# MINI_SAM_D21_r001_b001.net
KiCad netlist of a schematic drawn in EAGLE
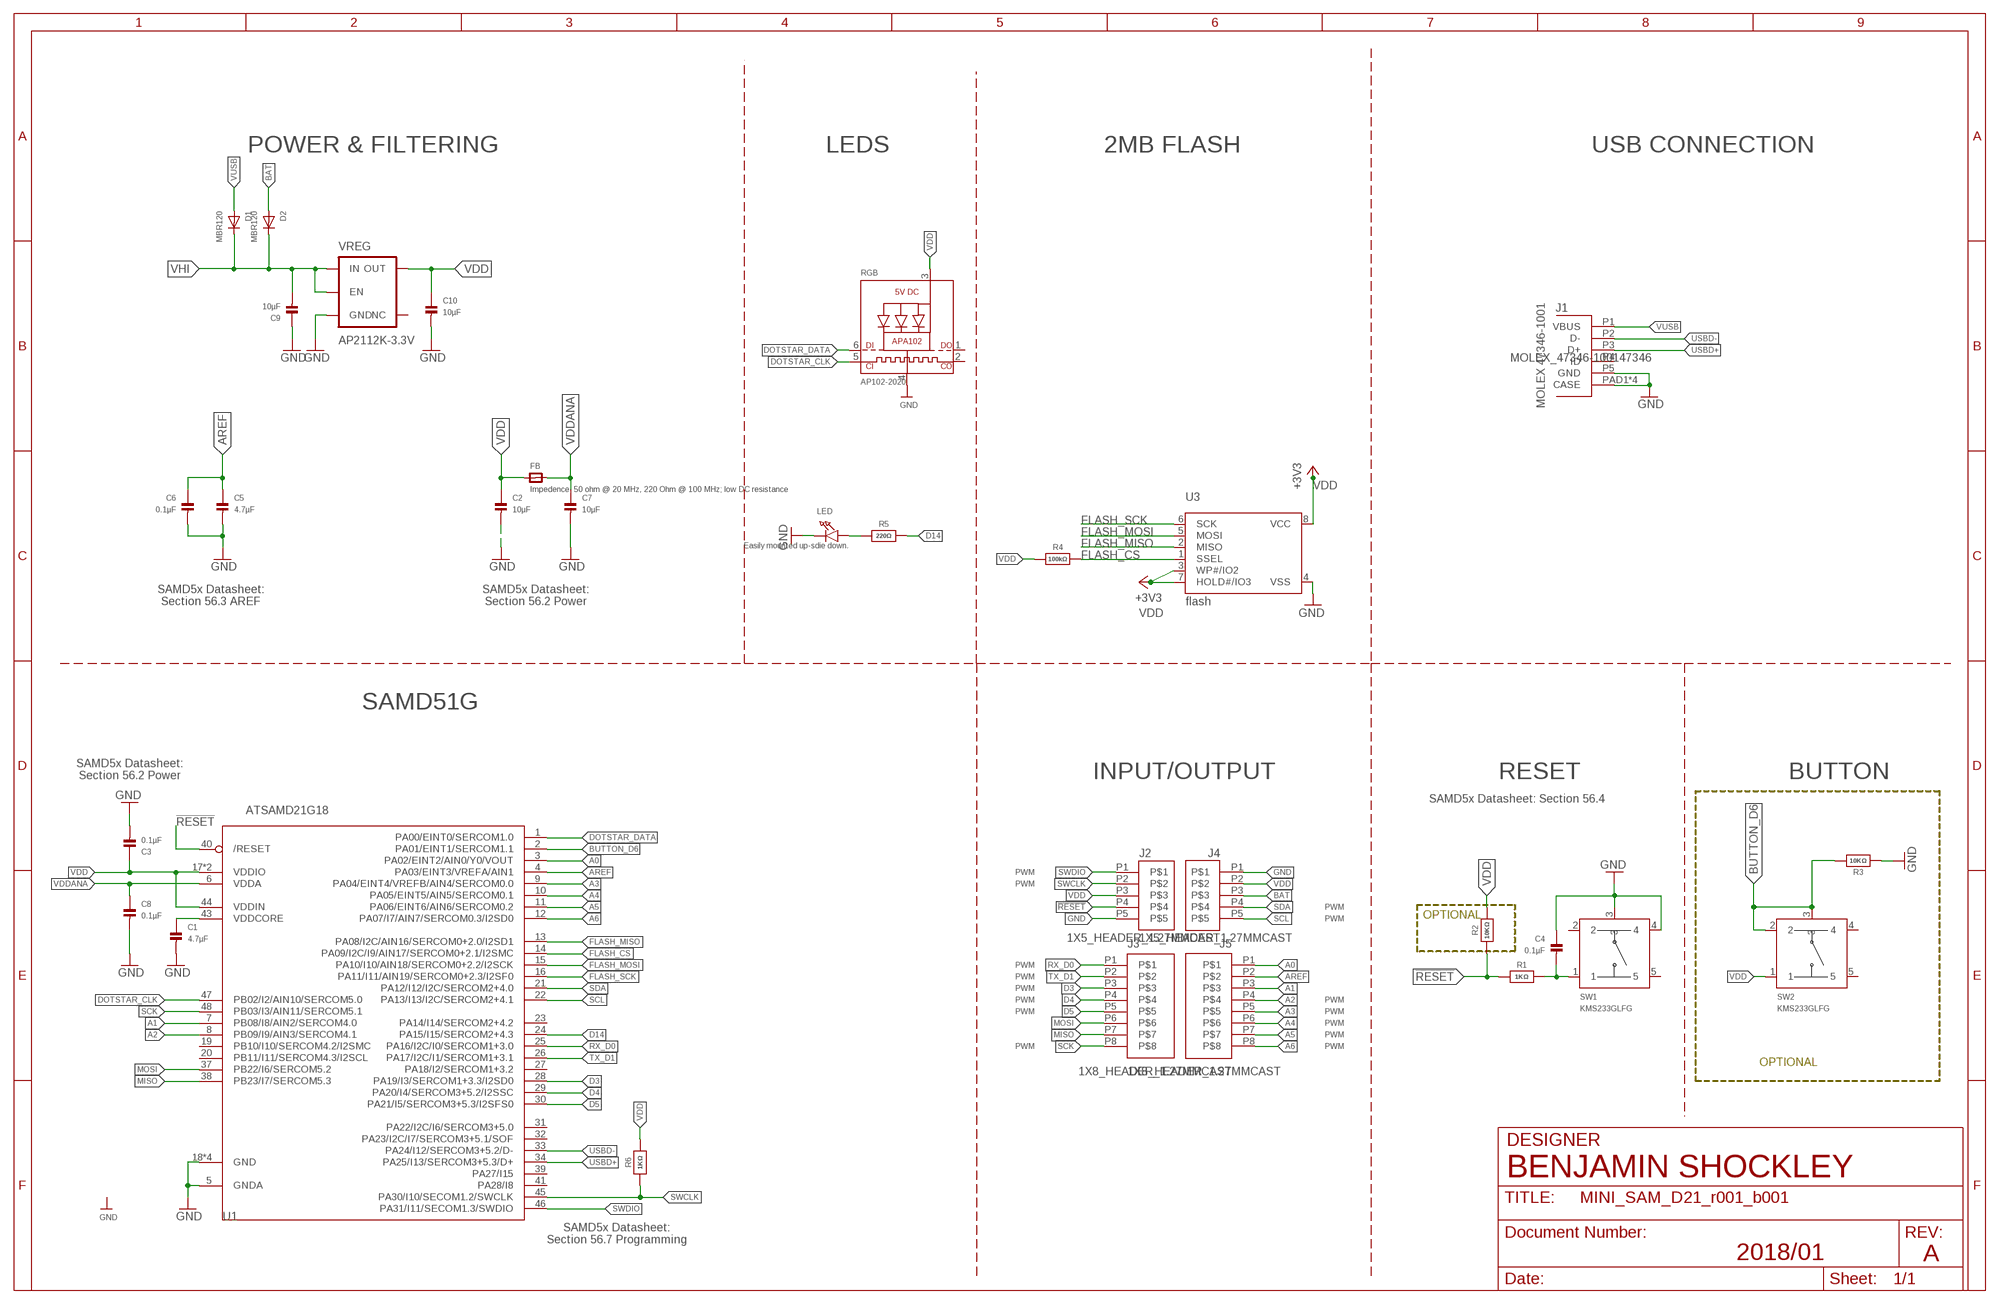
[diagram p0: schematic, sheet 1]

(export (version "E")
  (design (tool "Eeschema 10.0.6"))
  (components
    (comp (ref "C1")
      (value "4.7µF")
      (footprint "eagle-import:_0603MP")
      (libsource (lib "eagle-import") (part "CAP_CERAMIC_0603MP"))
    )
    (comp (ref "C2")
      (value "10µF")
      (footprint "eagle-import:_0603MP")
      (libsource (lib "eagle-import") (part "CAP_CERAMIC_0603MP"))
    )
    (comp (ref "C3")
      (value "0.1µF")
      (footprint "eagle-import:_0603MP")
      (libsource (lib "eagle-import") (part "CAP_CERAMIC_0603MP"))
    )
    (comp (ref "C4")
      (value "0.1µF")
      (footprint "eagle-import:_0603MP")
      (libsource (lib "eagle-import") (part "CAP_CERAMIC_0603MP"))
    )
    (comp (ref "C5")
      (value "4.7µF")
      (footprint "eagle-import:_0603MP")
      (libsource (lib "eagle-import") (part "CAP_CERAMIC_0603MP"))
    )
    (comp (ref "C6")
      (value "0.1µF")
      (footprint "eagle-import:_0603MP")
      (libsource (lib "eagle-import") (part "CAP_CERAMIC_0603MP"))
    )
    (comp (ref "C7")
      (value "10µF")
      (footprint "eagle-import:_0603MP")
      (libsource (lib "eagle-import") (part "CAP_CERAMIC_0603MP"))
    )
    (comp (ref "C8")
      (value "0.1µF")
      (footprint "eagle-import:_0603MP")
      (libsource (lib "eagle-import") (part "CAP_CERAMIC_0603MP"))
    )
    (comp (ref "C9")
      (value "10µF")
      (footprint "eagle-import:_0603MP")
      (libsource (lib "eagle-import") (part "CAP_CERAMIC_0603MP"))
    )
    (comp (ref "C10")
      (value "10µF")
      (footprint "eagle-import:_0603MP")
      (libsource (lib "eagle-import") (part "CAP_CERAMIC_0603MP"))
    )
    (comp (ref "D1")
      (value "MBR120")
      (footprint "eagle-import:SOD-123FL")
      (libsource (lib "eagle-import") (part "DIODE_SOD-123FL"))
    )
    (comp (ref "D2")
      (value "MBR120")
      (footprint "eagle-import:SOD-123FL")
      (libsource (lib "eagle-import") (part "DIODE_SOD-123FL"))
    )
    (comp (ref "FB")
      (value "Impedence: 50 ohm @ 20 MHz, 220 Ohm @ 100 MHz; low DC resistance")
      (footprint "eagle-import:_0603MP")
      (libsource (lib "eagle-import") (part "FERRITE_0603MP"))
    )
    (comp (ref "J1")
      (value "MOLEX_47346-100147346")
      (footprint "eagle-import:MOLEX_47346-1001")
      (libsource (lib "eagle-import") (part "MOLEX_47346-100147346"))
    )
    (comp (ref "J2")
      (value "1X5_HEADER_1.27MMCAST")
      (footprint "eagle-import:1X5_HEADER_1.27MM_CASTELLATED")
      (libsource (lib "eagle-import") (part "1X5_HEADER_1.27MMCAST"))
    )
    (comp (ref "J3")
      (value "1X8_HEADER_1.27MMCAST")
      (footprint "eagle-import:1X8_HEADER_1.27MM_CASTELLATED")
      (libsource (lib "eagle-import") (part "1X8_HEADER_1.27MMCAST"))
    )
    (comp (ref "J4")
      (value "1X5_HEADER_1.27MMCAST")
      (footprint "eagle-import:1X5_HEADER_1.27MM_CASTELLATED")
      (libsource (lib "eagle-import") (part "1X5_HEADER_1.27MMCAST"))
    )
    (comp (ref "J5")
      (value "1X8_HEADER_1.27MMCAST")
      (footprint "eagle-import:1X8_HEADER_1.27MM_CASTELLATED")
      (libsource (lib "eagle-import") (part "1X8_HEADER_1.27MMCAST"))
    )
    (comp (ref "LED")
      (value "Easily mounted up-sdie down.")
      (footprint "eagle-import:CHIPLED_0805_NOOUTLINE")
      (libsource (lib "eagle-import") (part "LED0805_NOOUTLINE"))
    )
    (comp (ref "R1")
      (value "1KΩ")
      (footprint "eagle-import:_0603MP")
      (libsource (lib "eagle-import") (part "RESISTOR_0603MP"))
    )
    (comp (ref "R2")
      (value "10KΩ")
      (footprint "eagle-import:_0603MP")
      (libsource (lib "eagle-import") (part "RESISTOR_0603MP"))
    )
    (comp (ref "R3")
      (value "10KΩ")
      (footprint "eagle-import:_0603MP")
      (libsource (lib "eagle-import") (part "RESISTOR_0603MP"))
    )
    (comp (ref "R4")
      (value "100kΩ")
      (footprint "eagle-import:_0603MP")
      (libsource (lib "eagle-import") (part "RESISTOR_0603MP"))
    )
    (comp (ref "R5")
      (value "220Ω")
      (footprint "eagle-import:_0603MP")
      (libsource (lib "eagle-import") (part "RESISTOR_0603MP"))
    )
    (comp (ref "R6")
      (value "1KΩ")
      (footprint "eagle-import:_0603MP")
      (libsource (lib "eagle-import") (part "RESISTOR_0603MP"))
    )
    (comp (ref "RGB")
      (value "AP102-2020")
      (footprint "eagle-import:APA102_2020")
      (libsource (lib "eagle-import") (part "APA1022020"))
    )
    (comp (ref "SW1")
      (value "KMS233GLFG")
      (footprint "eagle-import:KMS_SWITCH")
      (libsource (lib "eagle-import") (part "KMS_SWITCHKMS"))
    )
    (comp (ref "SW2")
      (value "KMS233GLFG")
      (footprint "eagle-import:KMS_SWITCH")
      (libsource (lib "eagle-import") (part "KMS_SWITCHKMS"))
    )
    (comp (ref "U1")
      (value "ATSAMD21G18")
      (footprint "eagle-import:TQFN48_7MM")
      (libsource (lib "eagle-import") (part "ATSAMD21G_QFN"))
    )
    (comp (ref "U3")
      (value "flash")
      (footprint "eagle-import:USON8")
      (libsource (lib "eagle-import") (part "SPIFLASH_8PINUX"))
    )
    (comp (ref "VREG")
      (value "AP2112K-3.3V")
      (footprint "eagle-import:SOT23-5")
      (libsource (lib "eagle-import") (part "V_REG_AP2112K-3.3V"))
    )
  )
  (nets
    (net (code "1") (name "/~{RESET}") (class "Default")
      (node (ref "J2") (pin "P4") (pinfunction "P$4_P4") (pintype "bidirectional"))
      (node (ref "R1") (pin "1") (pinfunction "1_1") (pintype "passive"))
      (node (ref "R2") (pin "1") (pinfunction "1_1") (pintype "passive"))
      (node (ref "U1") (pin "40") (pinfunction "/RESET_40") (pintype "bidirectional"))
    )
    (net (code "2") (name "A0") (class "Default")
      (node (ref "J5") (pin "P1") (pinfunction "P$1_P1") (pintype "bidirectional"))
      (node (ref "U1") (pin "3") (pinfunction "PA02/EINT2/AIN0/Y0/VOUT_3") (pintype "bidirectional"))
    )
    (net (code "3") (name "A1") (class "Default")
      (node (ref "J5") (pin "P3") (pinfunction "P$3_P3") (pintype "bidirectional"))
      (node (ref "U1") (pin "7") (pinfunction "PB08/I8/AIN2/SERCOM4.0_7") (pintype "bidirectional"))
    )
    (net (code "4") (name "A2") (class "Default")
      (node (ref "J5") (pin "P4") (pinfunction "P$4_P4") (pintype "bidirectional"))
      (node (ref "U1") (pin "8") (pinfunction "PB09/I9/AIN3/SERCOM4.1_8") (pintype "bidirectional"))
    )
    (net (code "5") (name "A3") (class "Default")
      (node (ref "J5") (pin "P5") (pinfunction "P$5_P5") (pintype "bidirectional"))
      (node (ref "U1") (pin "9") (pinfunction "PA04/EINT4/VREFB/AIN4/SERCOM0.0_9") (pintype "bidirectional"))
    )
    (net (code "6") (name "A4") (class "Default")
      (node (ref "J5") (pin "P6") (pinfunction "P$6_P6") (pintype "bidirectional"))
      (node (ref "U1") (pin "10") (pinfunction "PA05/EINT5/AIN5/SERCOM0.1_10") (pintype "bidirectional"))
    )
    (net (code "7") (name "A5") (class "Default")
      (node (ref "J5") (pin "P7") (pinfunction "P$7_P7") (pintype "bidirectional"))
      (node (ref "U1") (pin "11") (pinfunction "PA06/EINT6/AIN6/SERCOM0.2_11") (pintype "bidirectional"))
    )
    (net (code "8") (name "A6") (class "Default")
      (node (ref "J5") (pin "P8") (pinfunction "P$8_P8") (pintype "bidirectional"))
      (node (ref "U1") (pin "12") (pinfunction "PA07/I7/AIN7/SERCOM0.3/I2SD0_12") (pintype "bidirectional"))
    )
    (net (code "9") (name "AREF") (class "Default")
      (node (ref "C5") (pin "1") (pinfunction "P$1_1") (pintype "passive"))
      (node (ref "C6") (pin "1") (pinfunction "P$1_1") (pintype "passive"))
      (node (ref "J5") (pin "P2") (pinfunction "P$2_P2") (pintype "bidirectional"))
      (node (ref "U1") (pin "4") (pinfunction "PA03/EINT3/VREFA/AIN1_4") (pintype "bidirectional"))
    )
    (net (code "10") (name "BAT") (class "Default")
      (node (ref "D2") (pin "A") (pinfunction "A_A") (pintype "passive"))
      (node (ref "J4") (pin "P3") (pinfunction "P$3_P3") (pintype "bidirectional"))
    )
    (net (code "11") (name "BUTTON_D6") (class "Default")
      (node (ref "R3") (pin "2") (pinfunction "2_2") (pintype "passive"))
      (node (ref "SW2") (pin "2") (pinfunction "2_2") (pintype "bidirectional"))
      (node (ref "SW2") (pin "3") (pinfunction "3_3") (pintype "bidirectional"))
      (node (ref "U1") (pin "2") (pinfunction "PA01/EINT1/SERCOM1.1_2") (pintype "bidirectional"))
    )
    (net (code "12") (name "D3") (class "Default")
      (node (ref "J3") (pin "P3") (pinfunction "P$3_P3") (pintype "bidirectional"))
      (node (ref "U1") (pin "28") (pinfunction "PA19/I3/SERCOM1+3.3/I2SD0_28") (pintype "bidirectional"))
    )
    (net (code "13") (name "D4") (class "Default")
      (node (ref "J3") (pin "P4") (pinfunction "P$4_P4") (pintype "bidirectional"))
      (node (ref "U1") (pin "29") (pinfunction "PA20/I4/SERCOM3+5.2/I2SSC_29") (pintype "bidirectional"))
    )
    (net (code "14") (name "D5") (class "Default")
      (node (ref "J3") (pin "P5") (pinfunction "P$5_P5") (pintype "bidirectional"))
      (node (ref "U1") (pin "30") (pinfunction "PA21/I5/SERCOM3+5.3/I2SFS0_30") (pintype "bidirectional"))
    )
    (net (code "15") (name "D14") (class "Default")
      (node (ref "R5") (pin "2") (pinfunction "2_2") (pintype "passive"))
      (node (ref "U1") (pin "24") (pinfunction "PA15/I15/SERCOM2+4.3_24") (pintype "bidirectional"))
    )
    (net (code "16") (name "DOTSTAR_CLK") (class "Default")
      (node (ref "RGB") (pin "5") (pinfunction "CKI_5") (pintype "input"))
      (node (ref "U1") (pin "47") (pinfunction "PB02/I2/AIN10/SERCOM5.0_47") (pintype "bidirectional"))
    )
    (net (code "17") (name "DOTSTAR_DATA") (class "Default")
      (node (ref "RGB") (pin "6") (pinfunction "DI_6") (pintype "input"))
      (node (ref "U1") (pin "1") (pinfunction "PA00/EINT0/SERCOM1.0_1") (pintype "bidirectional"))
    )
    (net (code "18") (name "FLASH_CS") (class "Default")
      (node (ref "R4") (pin "2") (pinfunction "2_2") (pintype "passive"))
      (node (ref "U1") (pin "14") (pinfunction "PA09/I2C/I9/AIN17/SERCOM0+2.1/I2SMC_14") (pintype "bidirectional"))
      (node (ref "U3") (pin "1") (pinfunction "SSEL_1") (pintype "bidirectional"))
    )
    (net (code "19") (name "FLASH_MISO") (class "Default")
      (node (ref "U1") (pin "13") (pinfunction "PA08/I2C/AIN16/SERCOM0+2.0/I2SD1_13") (pintype "bidirectional"))
      (node (ref "U3") (pin "2") (pinfunction "MISO_2") (pintype "bidirectional"))
    )
    (net (code "20") (name "FLASH_MOSI") (class "Default")
      (node (ref "U1") (pin "15") (pinfunction "PA10/I10/AIN18/SERCOM0+2.2/I2SCK_15") (pintype "bidirectional"))
      (node (ref "U3") (pin "5") (pinfunction "MOSI_5") (pintype "bidirectional"))
    )
    (net (code "21") (name "FLASH_SCK") (class "Default")
      (node (ref "U1") (pin "16") (pinfunction "PA11/I11/AIN19/SERCOM0+2.3/I2SF0_16") (pintype "bidirectional"))
      (node (ref "U3") (pin "6") (pinfunction "SCK_6") (pintype "bidirectional"))
    )
    (net (code "22") (name "GND") (class "Default")
      (node (ref "C1") (pin "2") (pinfunction "P$2_2") (pintype "passive"))
      (node (ref "C10") (pin "2") (pinfunction "P$2_2") (pintype "passive"))
      (node (ref "C2") (pin "2") (pinfunction "P$2_2") (pintype "passive"))
      (node (ref "C3") (pin "2") (pinfunction "P$2_2") (pintype "passive"))
      (node (ref "C4") (pin "1") (pinfunction "P$1_1") (pintype "passive"))
      (node (ref "C5") (pin "2") (pinfunction "P$2_2") (pintype "passive"))
      (node (ref "C6") (pin "2") (pinfunction "P$2_2") (pintype "passive"))
      (node (ref "C7") (pin "2") (pinfunction "P$2_2") (pintype "passive"))
      (node (ref "C8") (pin "2") (pinfunction "P$2_2") (pintype "passive"))
      (node (ref "C9") (pin "1") (pinfunction "P$1_1") (pintype "passive"))
      (node (ref "J1") (pin "P5") (pinfunction "GND_P5") (pintype "power_in"))
      (node (ref "J1") (pin "PAD1") (pinfunction "CASE_PAD1") (pintype "bidirectional"))
      (node (ref "J1") (pin "PAD2") (pinfunction "CASE_PAD2") (pintype "bidirectional"))
      (node (ref "J1") (pin "PAD3") (pinfunction "CASE_PAD3") (pintype "bidirectional"))
      (node (ref "J1") (pin "PAD4") (pinfunction "CASE_PAD4") (pintype "bidirectional"))
      (node (ref "J2") (pin "P5") (pinfunction "P$5_P5") (pintype "bidirectional"))
      (node (ref "J4") (pin "P1") (pinfunction "P$1_P1") (pintype "bidirectional"))
      (node (ref "LED") (pin "C") (pinfunction "C_C") (pintype "passive"))
      (node (ref "R3") (pin "1") (pinfunction "1_1") (pintype "passive"))
      (node (ref "RGB") (pin "4") (pinfunction "GND_4") (pintype "power_in"))
      (node (ref "SW1") (pin "3") (pinfunction "3_3") (pintype "bidirectional"))
      (node (ref "SW1") (pin "4") (pinfunction "4_4") (pintype "bidirectional"))
      (node (ref "U1") (pin "18") (pinfunction "GND_18") (pintype "power_in"))
      (node (ref "U1") (pin "35") (pinfunction "GND_35") (pintype "power_in"))
      (node (ref "U1") (pin "42") (pinfunction "GND_42") (pintype "power_in"))
      (node (ref "U1") (pin "5") (pinfunction "GNDA_5") (pintype "power_in"))
      (node (ref "U1") (pin "THERMAL") (pinfunction "GND_THERMAL") (pintype "power_in"))
      (node (ref "U3") (pin "4") (pinfunction "VSS_4") (pintype "bidirectional"))
      (node (ref "VREG") (pin "2") (pinfunction "GND_2") (pintype "input"))
    )
    (net (code "23") (name "MISO") (class "Default")
      (node (ref "J3") (pin "P7") (pinfunction "P$7_P7") (pintype "bidirectional"))
      (node (ref "U1") (pin "38") (pinfunction "PB23/I7/SERCOM5.3_38") (pintype "bidirectional"))
    )
    (net (code "24") (name "MOSI") (class "Default")
      (node (ref "J3") (pin "P6") (pinfunction "P$6_P6") (pintype "bidirectional"))
      (node (ref "U1") (pin "37") (pinfunction "PB22/I6/SERCOM5.2_37") (pintype "bidirectional"))
    )
    (net (code "25") (name "Net-(C1-P$1)") (class "Default")
      (node (ref "C1") (pin "1") (pinfunction "P$1_1") (pintype "passive"))
      (node (ref "U1") (pin "43") (pinfunction "VDDCORE_43") (pintype "power_in"))
    )
    (net (code "26") (name "Net-(C4-P$2)") (class "Default")
      (node (ref "C4") (pin "2") (pinfunction "P$2_2") (pintype "passive"))
      (node (ref "R1") (pin "2") (pinfunction "2_2") (pintype "passive"))
      (node (ref "SW1") (pin "1") (pinfunction "1_1") (pintype "bidirectional"))
    )
    (net (code "27") (name "Net-(LED-PadA)") (class "Default")
      (node (ref "LED") (pin "A") (pinfunction "A_A") (pintype "passive"))
      (node (ref "R5") (pin "1") (pinfunction "1_1") (pintype "passive"))
    )
    (net (code "28") (name "RX_D0") (class "Default")
      (node (ref "J3") (pin "P1") (pinfunction "P$1_P1") (pintype "bidirectional"))
      (node (ref "U1") (pin "25") (pinfunction "PA16/I2C/I0/SERCOM1+3.0_25") (pintype "bidirectional"))
    )
    (net (code "29") (name "SCK") (class "Default")
      (node (ref "J3") (pin "P8") (pinfunction "P$8_P8") (pintype "bidirectional"))
      (node (ref "U1") (pin "48") (pinfunction "PB03/I3/AIN11/SERCOM5.1_48") (pintype "bidirectional"))
    )
    (net (code "30") (name "SCL") (class "Default")
      (node (ref "J4") (pin "P5") (pinfunction "P$5_P5") (pintype "bidirectional"))
      (node (ref "U1") (pin "22") (pinfunction "PA13/I13/I2C/SERCOM2+4.1_22") (pintype "bidirectional"))
    )
    (net (code "31") (name "SDA") (class "Default")
      (node (ref "J4") (pin "P4") (pinfunction "P$4_P4") (pintype "bidirectional"))
      (node (ref "U1") (pin "21") (pinfunction "PA12/I12/I2C/SERCOM2+4.0_21") (pintype "bidirectional"))
    )
    (net (code "32") (name "SWCLK") (class "Default")
      (node (ref "J2") (pin "P2") (pinfunction "P$2_P2") (pintype "bidirectional"))
      (node (ref "R6") (pin "1") (pinfunction "1_1") (pintype "passive"))
      (node (ref "U1") (pin "45") (pinfunction "PA30/I10/SECOM1.2/SWCLK_45") (pintype "bidirectional"))
    )
    (net (code "33") (name "SWDIO") (class "Default")
      (node (ref "J2") (pin "P1") (pinfunction "P$1_P1") (pintype "bidirectional"))
      (node (ref "U1") (pin "46") (pinfunction "PA31/I11/SECOM1.3/SWDIO_46") (pintype "bidirectional"))
    )
    (net (code "34") (name "TX_D1") (class "Default")
      (node (ref "J3") (pin "P2") (pinfunction "P$2_P2") (pintype "bidirectional"))
      (node (ref "U1") (pin "26") (pinfunction "PA17/I2C/I1/SERCOM1+3.1_26") (pintype "bidirectional"))
    )
    (net (code "35") (name "USBD+") (class "Default")
      (node (ref "J1") (pin "P3") (pinfunction "D+_P3") (pintype "bidirectional"))
      (node (ref "U1") (pin "34") (pinfunction "PA25/I13/SERCOM3+5.3/D+_34") (pintype "bidirectional"))
    )
    (net (code "36") (name "USBD-") (class "Default")
      (node (ref "J1") (pin "P2") (pinfunction "D-_P2") (pintype "bidirectional"))
      (node (ref "U1") (pin "33") (pinfunction "PA24/I12/SERCOM3+5.2/D-_33") (pintype "bidirectional"))
    )
    (net (code "37") (name "VDD") (class "Default")
      (node (ref "C10") (pin "1") (pinfunction "P$1_1") (pintype "passive"))
      (node (ref "C2") (pin "1") (pinfunction "P$1_1") (pintype "passive"))
      (node (ref "C3") (pin "1") (pinfunction "P$1_1") (pintype "passive"))
      (node (ref "FB") (pin "1") (pinfunction "P$1_1") (pintype "passive"))
      (node (ref "J2") (pin "P3") (pinfunction "P$3_P3") (pintype "bidirectional"))
      (node (ref "J4") (pin "P2") (pinfunction "P$2_P2") (pintype "bidirectional"))
      (node (ref "R2") (pin "2") (pinfunction "2_2") (pintype "passive"))
      (node (ref "R4") (pin "1") (pinfunction "1_1") (pintype "passive"))
      (node (ref "R6") (pin "2") (pinfunction "2_2") (pintype "passive"))
      (node (ref "RGB") (pin "3") (pinfunction "VDD_3") (pintype "power_in"))
      (node (ref "SW2") (pin "1") (pinfunction "1_1") (pintype "bidirectional"))
      (node (ref "U1") (pin "17") (pinfunction "VDDIO_17") (pintype "power_in"))
      (node (ref "U1") (pin "36") (pinfunction "VDDIO_36") (pintype "power_in"))
      (node (ref "U1") (pin "44") (pinfunction "VDDIN_44") (pintype "power_in"))
      (node (ref "U3") (pin "3") (pinfunction "WP#/IO2_3") (pintype "bidirectional"))
      (node (ref "U3") (pin "7") (pinfunction "HOLD#/IO3_7") (pintype "bidirectional"))
      (node (ref "U3") (pin "8") (pinfunction "VCC_8") (pintype "bidirectional"))
      (node (ref "VREG") (pin "5") (pinfunction "OUT_5") (pintype "passive"))
    )
    (net (code "38") (name "VDDANA") (class "Default")
      (node (ref "C7") (pin "1") (pinfunction "P$1_1") (pintype "passive"))
      (node (ref "C8") (pin "1") (pinfunction "P$1_1") (pintype "passive"))
      (node (ref "FB") (pin "2") (pinfunction "P$2_2") (pintype "passive"))
      (node (ref "U1") (pin "6") (pinfunction "VDDA_6") (pintype "power_in"))
    )
    (net (code "39") (name "VHI") (class "Default")
      (node (ref "C9") (pin "2") (pinfunction "P$2_2") (pintype "passive"))
      (node (ref "D1") (pin "C") (pinfunction "C_C") (pintype "passive"))
      (node (ref "D2") (pin "C") (pinfunction "C_C") (pintype "passive"))
      (node (ref "VREG") (pin "1") (pinfunction "IN_1") (pintype "input"))
      (node (ref "VREG") (pin "3") (pinfunction "EN_3") (pintype "input"))
    )
    (net (code "40") (name "VUSB") (class "Default")
      (node (ref "D1") (pin "A") (pinfunction "A_A") (pintype "passive"))
      (node (ref "J1") (pin "P1") (pinfunction "VBUS_P1") (pintype "power_in"))
    )
    (net (code "41") (name "unconnected-(J1-ID-PadP4)") (class "Default")
      (node (ref "J1") (pin "P4") (pinfunction "ID_P4") (pintype "bidirectional"))
    )
    (net (code "42") (name "unconnected-(RGB-CKO-Pad2)") (class "Default")
      (node (ref "RGB") (pin "2") (pinfunction "CKO_2") (pintype "output"))
    )
    (net (code "43") (name "unconnected-(RGB-DO-Pad1)") (class "Default")
      (node (ref "RGB") (pin "1") (pinfunction "DO_1") (pintype "output"))
    )
    (net (code "44") (name "unconnected-(SW1-Pad2)") (class "Default")
      (node (ref "SW1") (pin "2") (pinfunction "2_2") (pintype "bidirectional"))
    )
    (net (code "45") (name "unconnected-(SW1-Pad5)") (class "Default")
      (node (ref "SW1") (pin "5") (pinfunction "5_5") (pintype "bidirectional"))
    )
    (net (code "46") (name "unconnected-(SW2-Pad4)") (class "Default")
      (node (ref "SW2") (pin "4") (pinfunction "4_4") (pintype "bidirectional"))
    )
    (net (code "47") (name "unconnected-(SW2-Pad5)") (class "Default")
      (node (ref "SW2") (pin "5") (pinfunction "5_5") (pintype "bidirectional"))
    )
    (net (code "48") (name "unconnected-(U1-PA14{slash}I14{slash}SERCOM2+4.2-Pad23)") (class "Default")
      (node (ref "U1") (pin "23") (pinfunction "PA14/I14/SERCOM2+4.2_23") (pintype "bidirectional"))
    )
    (net (code "49") (name "unconnected-(U1-PA18{slash}I2{slash}SERCOM1+3.2-Pad27)") (class "Default")
      (node (ref "U1") (pin "27") (pinfunction "PA18/I2/SERCOM1+3.2_27") (pintype "bidirectional"))
    )
    (net (code "50") (name "unconnected-(U1-PA22{slash}I2C{slash}I6{slash}SERCOM3+5.0-Pad31)") (class "Default")
      (node (ref "U1") (pin "31") (pinfunction "PA22/I2C/I6/SERCOM3+5.0_31") (pintype "bidirectional"))
    )
    (net (code "51") (name "unconnected-(U1-PA23{slash}I2C{slash}I7{slash}SERCOM3+5.1{slash}SOF-Pad32)") (class "Default")
      (node (ref "U1") (pin "32") (pinfunction "PA23/I2C/I7/SERCOM3+5.1/SOF_32") (pintype "bidirectional"))
    )
    (net (code "52") (name "unconnected-(U1-PA27{slash}I15-Pad39)") (class "Default")
      (node (ref "U1") (pin "39") (pinfunction "PA27/I15_39") (pintype "bidirectional"))
    )
    (net (code "53") (name "unconnected-(U1-PA28{slash}I8-Pad41)") (class "Default")
      (node (ref "U1") (pin "41") (pinfunction "PA28/I8_41") (pintype "bidirectional"))
    )
    (net (code "54") (name "unconnected-(U1-PB10{slash}I10{slash}SERCOM4.2{slash}I2SMC-Pad19)") (class "Default")
      (node (ref "U1") (pin "19") (pinfunction "PB10/I10/SERCOM4.2/I2SMC_19") (pintype "bidirectional"))
    )
    (net (code "55") (name "unconnected-(U1-PB11{slash}I11{slash}SERCOM4.3{slash}I2SCL-Pad20)") (class "Default")
      (node (ref "U1") (pin "20") (pinfunction "PB11/I11/SERCOM4.3/I2SCL_20") (pintype "bidirectional"))
    )
    (net (code "56") (name "unconnected-(VREG-NC-Pad4)") (class "Default")
      (node (ref "VREG") (pin "4") (pinfunction "NC_4") (pintype "input"))
    )
  )
)
